# Winch.net
KiCad netlist of a schematic drawn in EAGLE
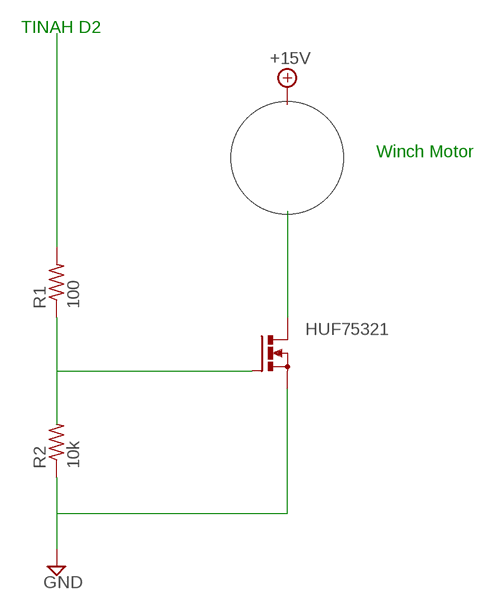
[diagram p0: schematic, sheet 1]

(export (version "E")
  (design (tool "Eeschema 10.0.6"))
  (components
    (comp (ref "HUF75321")
      (value "N-MOSFET-SO8S")
      (footprint "eagle-import:SO-08")
      (libsource (lib "eagle-import") (part "N-MOSFET-SO8S"))
    )
    (comp (ref "R1")
      (value "100")
      (footprint "eagle-import:0204V")
      (libsource (lib "eagle-import") (part "R-US_0204/2V"))
    )
    (comp (ref "R2")
      (value "10k")
      (footprint "eagle-import:0204V")
      (libsource (lib "eagle-import") (part "R-US_0204/2V"))
    )
  )
  (nets
    (net (code "2") (name "GND") (class "Default")
      (node (ref "HUF75321") (pin "1") (pinfunction "S_1") (pintype "passive"))
      (node (ref "HUF75321") (pin "2") (pinfunction "S_2") (pintype "passive"))
      (node (ref "HUF75321") (pin "3") (pinfunction "S_3") (pintype "passive"))
      (node (ref "R2") (pin "1") (pinfunction "1_1") (pintype "passive"))
    )
    (net (code "3") (name "Net-(HUF75321-D-Pad5)") (class "Default")
      (node (ref "HUF75321") (pin "5") (pinfunction "D_5") (pintype "passive"))
      (node (ref "HUF75321") (pin "6") (pinfunction "D_6") (pintype "passive"))
      (node (ref "HUF75321") (pin "7") (pinfunction "D_7") (pintype "passive"))
      (node (ref "HUF75321") (pin "8") (pinfunction "D_8") (pintype "passive"))
    )
    (net (code "4") (name "Net-(HUF75321-G)") (class "Default")
      (node (ref "HUF75321") (pin "4") (pinfunction "G_4") (pintype "passive"))
      (node (ref "R1") (pin "1") (pinfunction "1_1") (pintype "passive"))
      (node (ref "R2") (pin "2") (pinfunction "2_2") (pintype "passive"))
    )
    (net (code "5") (name "unconnected-(R1-Pad2)") (class "Default")
      (node (ref "R1") (pin "2") (pinfunction "2_2") (pintype "passive"))
    )
  )
)
